# RFID_Reader.net
KiCad netlist of a schematic drawn in Altium Designer
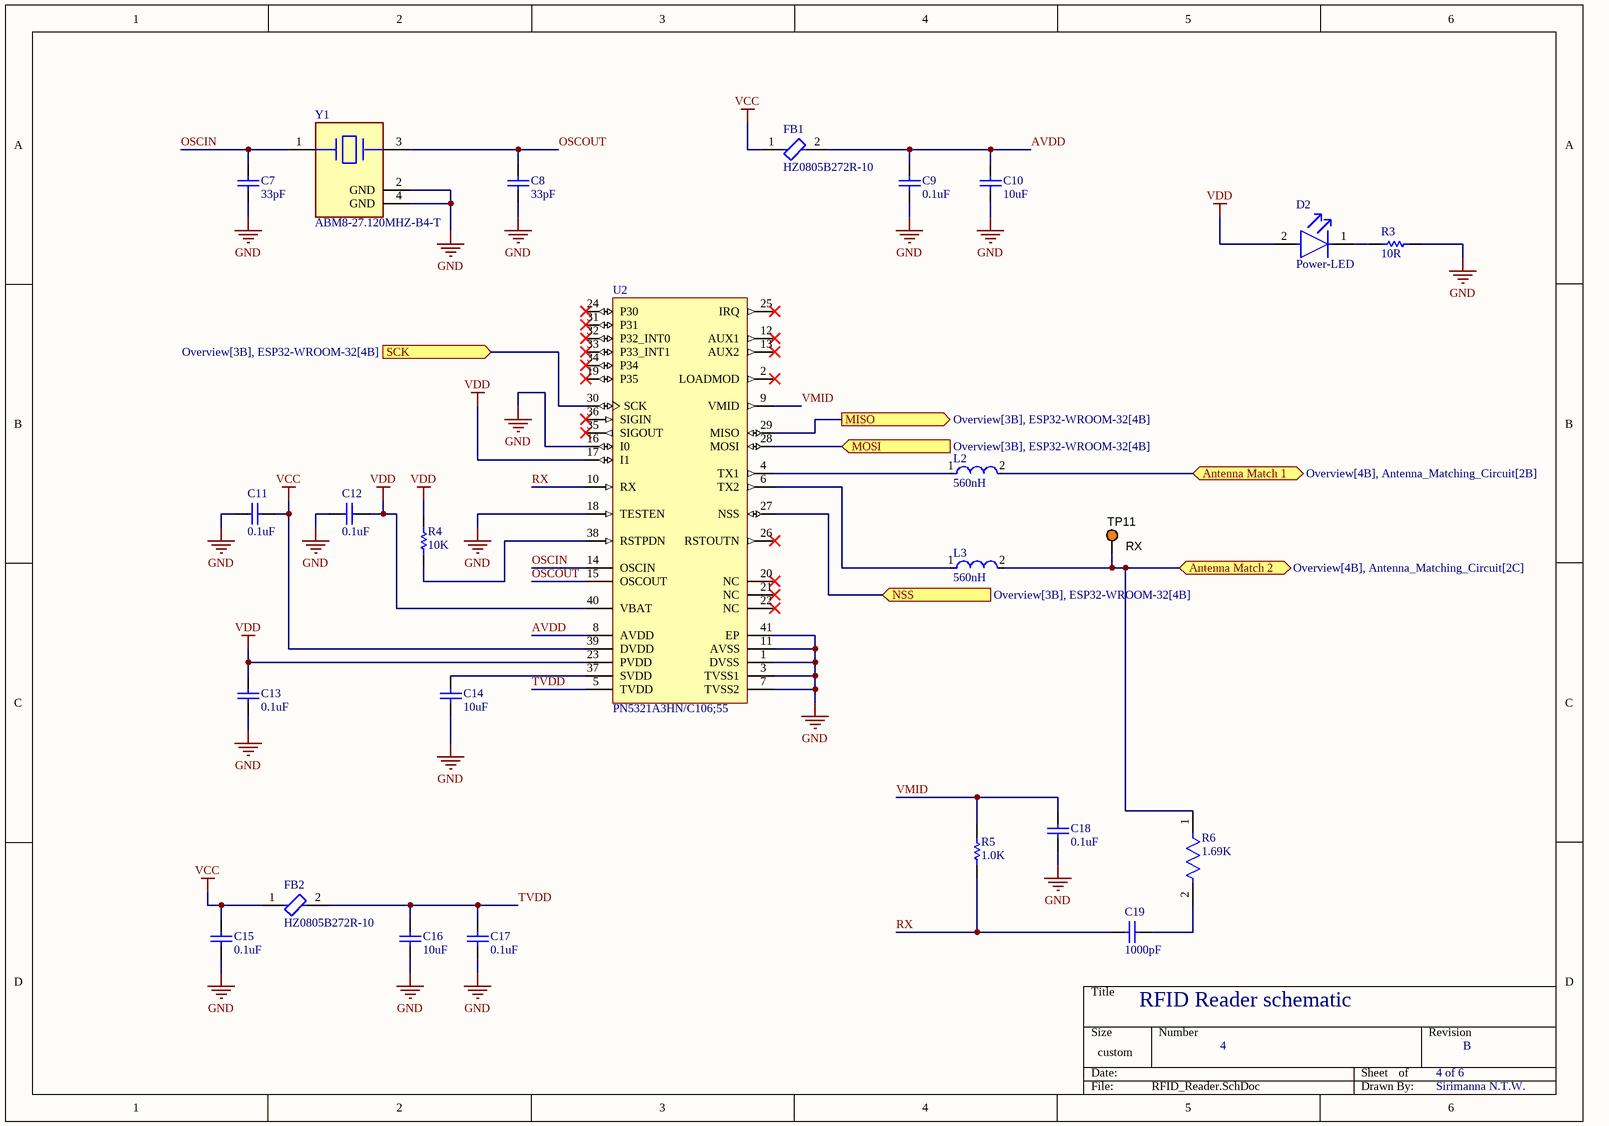
[diagram p0: RFID_Reader.SchDoc]

(export (version "E")
  (design (tool "Eeschema 10.0.6"))
  (components
    (comp (ref "C7")
      (value "33pF")
      (footprint "CAPC2013X135X45NL10T25")
      (description "Chip Capacitor, 0.1 uF, +/- 10%, 50 V, -55 to 125 degC, 0805 (2012 Metric), RoHS, Tape and Reel")
      (fields (field (name "VOLTAGE") "50V") (field (name "TOLERANCE") "10%"))
      (libsource (lib "Altium Content Vault") (part "CAP-NP-2"))
    )
    (comp (ref "C8")
      (value "33pF")
      (footprint "CAPC2013X135X45NL10T25")
      (description "Chip Capacitor, 0.1 uF, +/- 10%, 50 V, -55 to 125 degC, 0805 (2012 Metric), RoHS, Tape and Reel")
      (fields (field (name "VOLTAGE") "50V") (field (name "TOLERANCE") "10%"))
      (libsource (lib "Altium Content Vault") (part "CAP-NP-2"))
    )
    (comp (ref "C9")
      (value "0.1uF")
      (footprint "CAPC2013X135X45NL10T25")
      (description "Chip Capacitor, 0.1 uF, +/- 10%, 50 V, -55 to 125 degC, 0805 (2012 Metric), RoHS, Tape and Reel")
      (fields (field (name "VOLTAGE") "50V") (field (name "TOLERANCE") "10%"))
      (libsource (lib "Altium Content Vault") (part "CAP-NP-2"))
    )
    (comp (ref "C10")
      (value "10uF")
      (footprint "CAPC2013X135X45NL10T25")
      (description "Chip Capacitor, 0.1 uF, +/- 10%, 50 V, -55 to 125 degC, 0805 (2012 Metric), RoHS, Tape and Reel")
      (fields (field (name "VOLTAGE") "50V") (field (name "TOLERANCE") "10%"))
      (libsource (lib "Altium Content Vault") (part "CAP-NP-2"))
    )
    (comp (ref "C11")
      (value "0.1uF")
      (footprint "CAPC2013X135X45NL10T25")
      (description "Chip Capacitor, 0.1 uF, +/- 10%, 50 V, -55 to 125 degC, 0805 (2012 Metric), RoHS, Tape and Reel")
      (fields (field (name "VOLTAGE") "50V") (field (name "TOLERANCE") "10%"))
      (libsource (lib "Altium Content Vault") (part "CAP-NP-2"))
    )
    (comp (ref "C12")
      (value "0.1uF")
      (footprint "CAPC2013X135X45NL10T25")
      (description "Chip Capacitor, 0.1 uF, +/- 10%, 50 V, -55 to 125 degC, 0805 (2012 Metric), RoHS, Tape and Reel")
      (fields (field (name "VOLTAGE") "50V") (field (name "TOLERANCE") "10%"))
      (libsource (lib "Altium Content Vault") (part "CAP-NP-2"))
    )
    (comp (ref "C13")
      (value "0.1uF")
      (footprint "CAPC2013X135X45NL10T25")
      (description "Chip Capacitor, 0.1 uF, +/- 10%, 50 V, -55 to 125 degC, 0805 (2012 Metric), RoHS, Tape and Reel")
      (fields (field (name "VOLTAGE") "50V") (field (name "TOLERANCE") "10%"))
      (libsource (lib "Altium Content Vault") (part "CAP-NP-2"))
    )
    (comp (ref "C14")
      (value "10uF")
      (footprint "CAPC2013X135X45NL10T25")
      (description "Chip Capacitor, 0.1 uF, +/- 10%, 50 V, -55 to 125 degC, 0805 (2012 Metric), RoHS, Tape and Reel")
      (fields (field (name "VOLTAGE") "50V") (field (name "TOLERANCE") "10%"))
      (libsource (lib "Altium Content Vault") (part "CAP-NP-2"))
    )
    (comp (ref "C15")
      (value "0.1uF")
      (footprint "CAPC2013X135X45NL10T25")
      (description "Chip Capacitor, 0.1 uF, +/- 10%, 50 V, -55 to 125 degC, 0805 (2012 Metric), RoHS, Tape and Reel")
      (fields (field (name "VOLTAGE") "50V") (field (name "TOLERANCE") "10%"))
      (libsource (lib "Altium Content Vault") (part "CAP-NP-2"))
    )
    (comp (ref "C16")
      (value "10uF")
      (footprint "CAPC2013X135X45NL10T25")
      (description "Chip Capacitor, 0.1 uF, +/- 10%, 50 V, -55 to 125 degC, 0805 (2012 Metric), RoHS, Tape and Reel")
      (fields (field (name "VOLTAGE") "50V") (field (name "TOLERANCE") "10%"))
      (libsource (lib "Altium Content Vault") (part "CAP-NP-2"))
    )
    (comp (ref "C17")
      (value "0.1uF")
      (footprint "CAPC2013X135X45NL10T25")
      (description "Chip Capacitor, 0.1 uF, +/- 10%, 50 V, -55 to 125 degC, 0805 (2012 Metric), RoHS, Tape and Reel")
      (fields (field (name "VOLTAGE") "50V") (field (name "TOLERANCE") "10%"))
      (libsource (lib "Altium Content Vault") (part "CAP-NP-2"))
    )
    (comp (ref "C18")
      (value "0.1uF")
      (footprint "CAPC2013X135X45NL10T25")
      (description "Chip Capacitor, 0.1 uF, +/- 10%, 50 V, -55 to 125 degC, 0805 (2012 Metric), RoHS, Tape and Reel")
      (fields (field (name "VOLTAGE") "50V") (field (name "TOLERANCE") "10%"))
      (libsource (lib "Altium Content Vault") (part "CAP-NP-2"))
    )
    (comp (ref "C19")
      (value "1000pF")
      (footprint "CAPC2013X135X45NL10T25")
      (description "Chip Capacitor, 0.1 uF, +/- 10%, 50 V, -55 to 125 degC, 0805 (2012 Metric), RoHS, Tape and Reel")
      (fields (field (name "VOLTAGE") "50V") (field (name "TOLERANCE") "10%"))
      (libsource (lib "Altium Content Vault") (part "CAP-NP-2"))
    )
    (comp (ref "D2")
      (value "Power-LED")
      (footprint "FP-6_544-5255_01-4-MFG")
      (description "TLLG4400 Led, Pcb, Green, 0.63MCD, 3MM, T-1, 7MA, 1.9V, 565NM, 25DEG, 20V, 20MW, -40")
      (libsource (lib "Altium Content Vault") (part "8706943c75ba83719d021d2fdc84c58"))
    )
    (comp (ref "FB1")
      (value "HZ0805B272R-10")
      (footprint "FP-MPZ2012-MFG")
      (description "FERRITE BEAD 100 OHM 0805 1LN")
      (fields (field (name "TOLERANCE") "25%"))
      (libsource (lib "Altium Content Vault") (part "5f30dd21d616792df468990f7003faa"))
    )
    (comp (ref "FB2")
      (value "HZ0805B272R-10")
      (footprint "FP-MPZ2012-MFG")
      (description "FERRITE BEAD 100 OHM 0805 1LN")
      (fields (field (name "TOLERANCE") "25%"))
      (libsource (lib "Altium Content Vault") (part "5f30dd21d616792df468990f7003faa"))
    )
    (comp (ref "L2")
      (value "560nH")
      (footprint "FP-LQM21DN_00-IPC_C")
      (description "Multilayer Type Inductor for General Circuits, 0805 (2012), 0.56μH, 10%, 0.63Ω, 150mA")
      (fields (field (name "TOLERANCE") "10%"))
      (libsource (lib "Altium Content Vault") (part "725321dda6339637d4d059423bc1c3c"))
    )
    (comp (ref "L3")
      (value "560nH")
      (footprint "FP-LQM21DN_00-IPC_C")
      (description "Multilayer Type Inductor for General Circuits, 0805 (2012), 0.56μH, 10%, 0.63Ω, 150mA")
      (fields (field (name "TOLERANCE") "10%"))
      (libsource (lib "Altium Content Vault") (part "725321dda6339637d4d059423bc1c3c"))
    )
    (comp (ref "R3")
      (value "10R")
      (footprint "RESC2013X60X35ML10T20")
      (description "Chip Resistor, 10 Ohm, +/- 1%, 0.125 W, -55 to 155 degC, 0805 (2012 Metric), RoHS, Tape and Reel")
      (fields (field (name "MANUFACTURER") "Yageo") (field (name "TOLERANCE") "1%"))
      (libsource (lib "Altium Content Vault") (part "RES-2"))
    )
    (comp (ref "R4")
      (value "10K")
      (footprint "RESC2013X60X35NL10T20")
      (description "Chip Resistor, 10 KOhm, +/- 1%, 0.125 W, -55 to 155 degC, 0805 (2012 Metric), RoHS, Tape and Reel")
      (fields (field (name "MANUFACTURER") "Yageo"))
      (libsource (lib "Altium Content Vault") (part "RES-2"))
    )
    (comp (ref "R5")
      (value "1.0K")
      (footprint "RESC2013X50X30NL20T20")
      (fields (field (name "PART NUMBER") "CRCW08051K00FKEA") (field (name "MANUFACTURER") "Vishay Dale"))
      (libsource (lib "Altium Content Vault") (part "RES"))
    )
    (comp (ref "R6")
      (value "1.69K")
      (footprint "FP-CRCW0805-e3-MFG")
      (description "RES Thick Film, 1.5kΩ, 1%, 0.125W, 100ppm/°C, 0805")
      (fields (field (name "TOLERANCE") "1%"))
      (libsource (lib "Altium Content Vault") (part "1029c3af85768c4190bb7ad29bc67b5"))
    )
    (comp (ref "TP11")
      (value "RX")
      (footprint "KSTN-5003")
      (description "Test Point, Orange, 1-Pin THD, RoHS")
      (libsource (lib "Altium Content Vault") (part "TESTPOINT_ORANGE"))
    )
    (comp (ref "U2")
      (value "PN5321A3HN/C106;55")
      (footprint "NXP-HVQFN-40_L")
      (description "NFC Controller, 13.56 MHz, -30 to 85 degC, 40-Pin HVQFN (SOT618-1), RoHS, Tray")
      (fields (field (name "MANUFACTURER") "NXP Semiconductors"))
      (libsource (lib "Altium Content Vault") (part "NXP-PN5321A3HN-HVQFN-40"))
    )
    (comp (ref "Y1")
      (value "ABM8-27.120MHZ-B4-T")
      (footprint "FP-ABM8-MFG")
      (description "Crystal 27.12MHz ±30ppm 18pF SMD-4 3.2mm x 2.5mm")
      (libsource (lib "Altium Content Vault") (part "dfdb7f9a12507849fb681da9a70121c"))
    )
  )
  (nets
    (net (code "1") (name "/AVDD") (class "Default")
      (node (ref "C10") (pin "2") (pinfunction "2_2") (pintype "passive"))
      (node (ref "C9") (pin "2") (pinfunction "2_2") (pintype "passive"))
      (node (ref "FB1") (pin "2") (pinfunction "2_2") (pintype "passive"))
      (node (ref "U2") (pin "8") (pinfunction "AVDD_8") (pintype "power_in"))
    )
    (net (code "2") (name "/Antenna Match 1") (class "Default")
      (node (ref "L2") (pin "2") (pinfunction "2_2") (pintype "passive"))
    )
    (net (code "3") (name "/Antenna Match 2") (class "Default")
      (node (ref "L3") (pin "2") (pinfunction "2_2") (pintype "passive"))
      (node (ref "R6") (pin "1") (pinfunction "1_1") (pintype "passive"))
      (node (ref "TP11") (pin "1") (pinfunction "1_1") (pintype "passive"))
    )
    (net (code "4") (name "/MISO") (class "Default")
      (node (ref "U2") (pin "29") (pinfunction "MISO_29") (pintype "bidirectional"))
    )
    (net (code "5") (name "/MOSI") (class "Default")
      (node (ref "U2") (pin "28") (pinfunction "MOSI_28") (pintype "bidirectional"))
    )
    (net (code "6") (name "/NSS") (class "Default")
      (node (ref "U2") (pin "27") (pinfunction "NSS_27") (pintype "bidirectional"))
    )
    (net (code "7") (name "/OSCIN") (class "Default")
      (node (ref "C7") (pin "2") (pinfunction "2_2") (pintype "passive"))
      (node (ref "U2") (pin "14") (pinfunction "OSCIN_14") (pintype "passive"))
      (node (ref "Y1") (pin "1") (pinfunction "1_1") (pintype "passive"))
    )
    (net (code "8") (name "/OSCOUT") (class "Default")
      (node (ref "C8") (pin "2") (pinfunction "2_2") (pintype "passive"))
      (node (ref "U2") (pin "15") (pinfunction "OSCOUT_15") (pintype "passive"))
      (node (ref "Y1") (pin "3") (pinfunction "3_3") (pintype "passive"))
    )
    (net (code "9") (name "/RX") (class "Default")
      (node (ref "C19") (pin "1") (pinfunction "1_1") (pintype "passive"))
      (node (ref "R5") (pin "1") (pinfunction "1_1") (pintype "passive"))
      (node (ref "U2") (pin "10") (pinfunction "RX_10") (pintype "input"))
    )
    (net (code "10") (name "/SCK") (class "Default")
      (node (ref "U2") (pin "30") (pinfunction "SCK_30") (pintype "bidirectional"))
    )
    (net (code "11") (name "/TVDD") (class "Default")
      (node (ref "C16") (pin "2") (pinfunction "2_2") (pintype "passive"))
      (node (ref "C17") (pin "2") (pinfunction "2_2") (pintype "passive"))
      (node (ref "FB2") (pin "2") (pinfunction "2_2") (pintype "passive"))
      (node (ref "U2") (pin "5") (pinfunction "TVDD_5") (pintype "power_in"))
    )
    (net (code "12") (name "/VMID") (class "Default")
      (node (ref "C18") (pin "2") (pinfunction "2_2") (pintype "passive"))
      (node (ref "R5") (pin "2") (pinfunction "2_2") (pintype "passive"))
      (node (ref "U2") (pin "9") (pinfunction "VMID_9") (pintype "output"))
    )
    (net (code "13") (name "GND") (class "Default")
      (node (ref "C10") (pin "1") (pinfunction "1_1") (pintype "passive"))
      (node (ref "C11") (pin "2") (pinfunction "2_2") (pintype "passive"))
      (node (ref "C12") (pin "2") (pinfunction "2_2") (pintype "passive"))
      (node (ref "C13") (pin "1") (pinfunction "1_1") (pintype "passive"))
      (node (ref "C14") (pin "1") (pinfunction "1_1") (pintype "passive"))
      (node (ref "C15") (pin "1") (pinfunction "1_1") (pintype "passive"))
      (node (ref "C16") (pin "1") (pinfunction "1_1") (pintype "passive"))
      (node (ref "C17") (pin "1") (pinfunction "1_1") (pintype "passive"))
      (node (ref "C18") (pin "1") (pinfunction "1_1") (pintype "passive"))
      (node (ref "C7") (pin "1") (pinfunction "1_1") (pintype "passive"))
      (node (ref "C8") (pin "1") (pinfunction "1_1") (pintype "passive"))
      (node (ref "C9") (pin "1") (pinfunction "1_1") (pintype "passive"))
      (node (ref "R3") (pin "2") (pinfunction "2_2") (pintype "passive"))
      (node (ref "U2") (pin "1") (pinfunction "DVSS_1") (pintype "power_in"))
      (node (ref "U2") (pin "11") (pinfunction "AVSS_11") (pintype "power_in"))
      (node (ref "U2") (pin "16") (pinfunction "I0_16") (pintype "bidirectional"))
      (node (ref "U2") (pin "18") (pinfunction "TESTEN_18") (pintype "input"))
      (node (ref "U2") (pin "3") (pinfunction "TVSS1_3") (pintype "power_in"))
      (node (ref "U2") (pin "41") (pinfunction "EP_41") (pintype "passive"))
      (node (ref "U2") (pin "7") (pinfunction "TVSS2_7") (pintype "power_in"))
      (node (ref "Y1") (pin "2") (pinfunction "GND_2") (pintype "power_in"))
      (node (ref "Y1") (pin "4") (pinfunction "GND_4") (pintype "power_in"))
    )
    (net (code "14") (name "Net-(C19-Pad2)") (class "Default")
      (node (ref "C19") (pin "2") (pinfunction "2_2") (pintype "passive"))
      (node (ref "R6") (pin "2") (pinfunction "2_2") (pintype "passive"))
    )
    (net (code "15") (name "Net-(D2-C)") (class "Default")
      (node (ref "D2") (pin "1") (pinfunction "C_1") (pintype "passive"))
      (node (ref "R3") (pin "1") (pinfunction "1_1") (pintype "passive"))
    )
    (net (code "16") (name "Net-(U2-RSTPDN)") (class "Default")
      (node (ref "R4") (pin "1") (pinfunction "1_1") (pintype "passive"))
      (node (ref "U2") (pin "38") (pinfunction "RSTPDN_38") (pintype "input"))
    )
    (net (code "17") (name "Net-(U2-SVDD)") (class "Default")
      (node (ref "C14") (pin "2") (pinfunction "2_2") (pintype "passive"))
      (node (ref "U2") (pin "37") (pinfunction "SVDD_37") (pintype "power_in"))
    )
    (net (code "18") (name "Net-(U2-TX1)") (class "Default")
      (node (ref "L2") (pin "1") (pinfunction "1_1") (pintype "passive"))
      (node (ref "U2") (pin "4") (pinfunction "TX1_4") (pintype "output"))
    )
    (net (code "19") (name "Net-(U2-TX2)") (class "Default")
      (node (ref "L3") (pin "1") (pinfunction "1_1") (pintype "passive"))
      (node (ref "U2") (pin "6") (pinfunction "TX2_6") (pintype "output"))
    )
    (net (code "20") (name "VCC") (class "Default")
      (node (ref "C11") (pin "1") (pinfunction "1_1") (pintype "passive"))
      (node (ref "C15") (pin "2") (pinfunction "2_2") (pintype "passive"))
      (node (ref "FB1") (pin "1") (pinfunction "1_1") (pintype "passive"))
      (node (ref "FB2") (pin "1") (pinfunction "1_1") (pintype "passive"))
      (node (ref "U2") (pin "39") (pinfunction "DVDD_39") (pintype "power_in"))
    )
    (net (code "21") (name "VDD") (class "Default")
      (node (ref "C12") (pin "1") (pinfunction "1_1") (pintype "passive"))
      (node (ref "C13") (pin "2") (pinfunction "2_2") (pintype "passive"))
      (node (ref "D2") (pin "2") (pinfunction "A_2") (pintype "passive"))
      (node (ref "R4") (pin "2") (pinfunction "2_2") (pintype "passive"))
      (node (ref "U2") (pin "17") (pinfunction "I1_17") (pintype "bidirectional"))
      (node (ref "U2") (pin "23") (pinfunction "PVDD_23") (pintype "power_in"))
      (node (ref "U2") (pin "40") (pinfunction "VBAT_40") (pintype "power_in"))
    )
    (net (code "22") (name "unconnected-(U2-AUX1-Pad12)") (class "Default")
      (node (ref "U2") (pin "12") (pinfunction "AUX1_12") (pintype "output+no_connect"))
    )
    (net (code "23") (name "unconnected-(U2-AUX2-Pad13)") (class "Default")
      (node (ref "U2") (pin "13") (pinfunction "AUX2_13") (pintype "output+no_connect"))
    )
    (net (code "24") (name "unconnected-(U2-IRQ-Pad25)") (class "Default")
      (node (ref "U2") (pin "25") (pinfunction "IRQ_25") (pintype "output+no_connect"))
    )
    (net (code "25") (name "unconnected-(U2-LOADMOD-Pad2)") (class "Default")
      (node (ref "U2") (pin "2") (pinfunction "LOADMOD_2") (pintype "output+no_connect"))
    )
    (net (code "26") (name "unconnected-(U2-NC-Pad20)") (class "Default")
      (node (ref "U2") (pin "20") (pinfunction "NC_20") (pintype "passive+no_connect"))
    )
    (net (code "27") (name "unconnected-(U2-NC-Pad21)") (class "Default")
      (node (ref "U2") (pin "21") (pinfunction "NC_21") (pintype "passive+no_connect"))
    )
    (net (code "28") (name "unconnected-(U2-NC-Pad22)") (class "Default")
      (node (ref "U2") (pin "22") (pinfunction "NC_22") (pintype "passive+no_connect"))
    )
    (net (code "29") (name "unconnected-(U2-P30-Pad24)") (class "Default")
      (node (ref "U2") (pin "24") (pinfunction "P30_24") (pintype "bidirectional+no_connect"))
    )
    (net (code "30") (name "unconnected-(U2-P31-Pad31)") (class "Default")
      (node (ref "U2") (pin "31") (pinfunction "P31_31") (pintype "bidirectional+no_connect"))
    )
    (net (code "31") (name "unconnected-(U2-P32_INT0-Pad32)") (class "Default")
      (node (ref "U2") (pin "32") (pinfunction "P32_INT0_32") (pintype "bidirectional+no_connect"))
    )
    (net (code "32") (name "unconnected-(U2-P33_INT1-Pad33)") (class "Default")
      (node (ref "U2") (pin "33") (pinfunction "P33_INT1_33") (pintype "bidirectional+no_connect"))
    )
    (net (code "33") (name "unconnected-(U2-P34-Pad34)") (class "Default")
      (node (ref "U2") (pin "34") (pinfunction "P34_34") (pintype "bidirectional+no_connect"))
    )
    (net (code "34") (name "unconnected-(U2-P35-Pad19)") (class "Default")
      (node (ref "U2") (pin "19") (pinfunction "P35_19") (pintype "bidirectional+no_connect"))
    )
    (net (code "35") (name "unconnected-(U2-RSTOUTN-Pad26)") (class "Default")
      (node (ref "U2") (pin "26") (pinfunction "RSTOUTN_26") (pintype "output+no_connect"))
    )
    (net (code "36") (name "unconnected-(U2-SIGIN-Pad36)") (class "Default")
      (node (ref "U2") (pin "36") (pinfunction "SIGIN_36") (pintype "input+no_connect"))
    )
    (net (code "37") (name "unconnected-(U2-SIGOUT-Pad35)") (class "Default")
      (node (ref "U2") (pin "35") (pinfunction "SIGOUT_35") (pintype "output+no_connect"))
    )
  )
)
